# Schema.net
KiCad netlist of a schematic drawn in Altium Designer
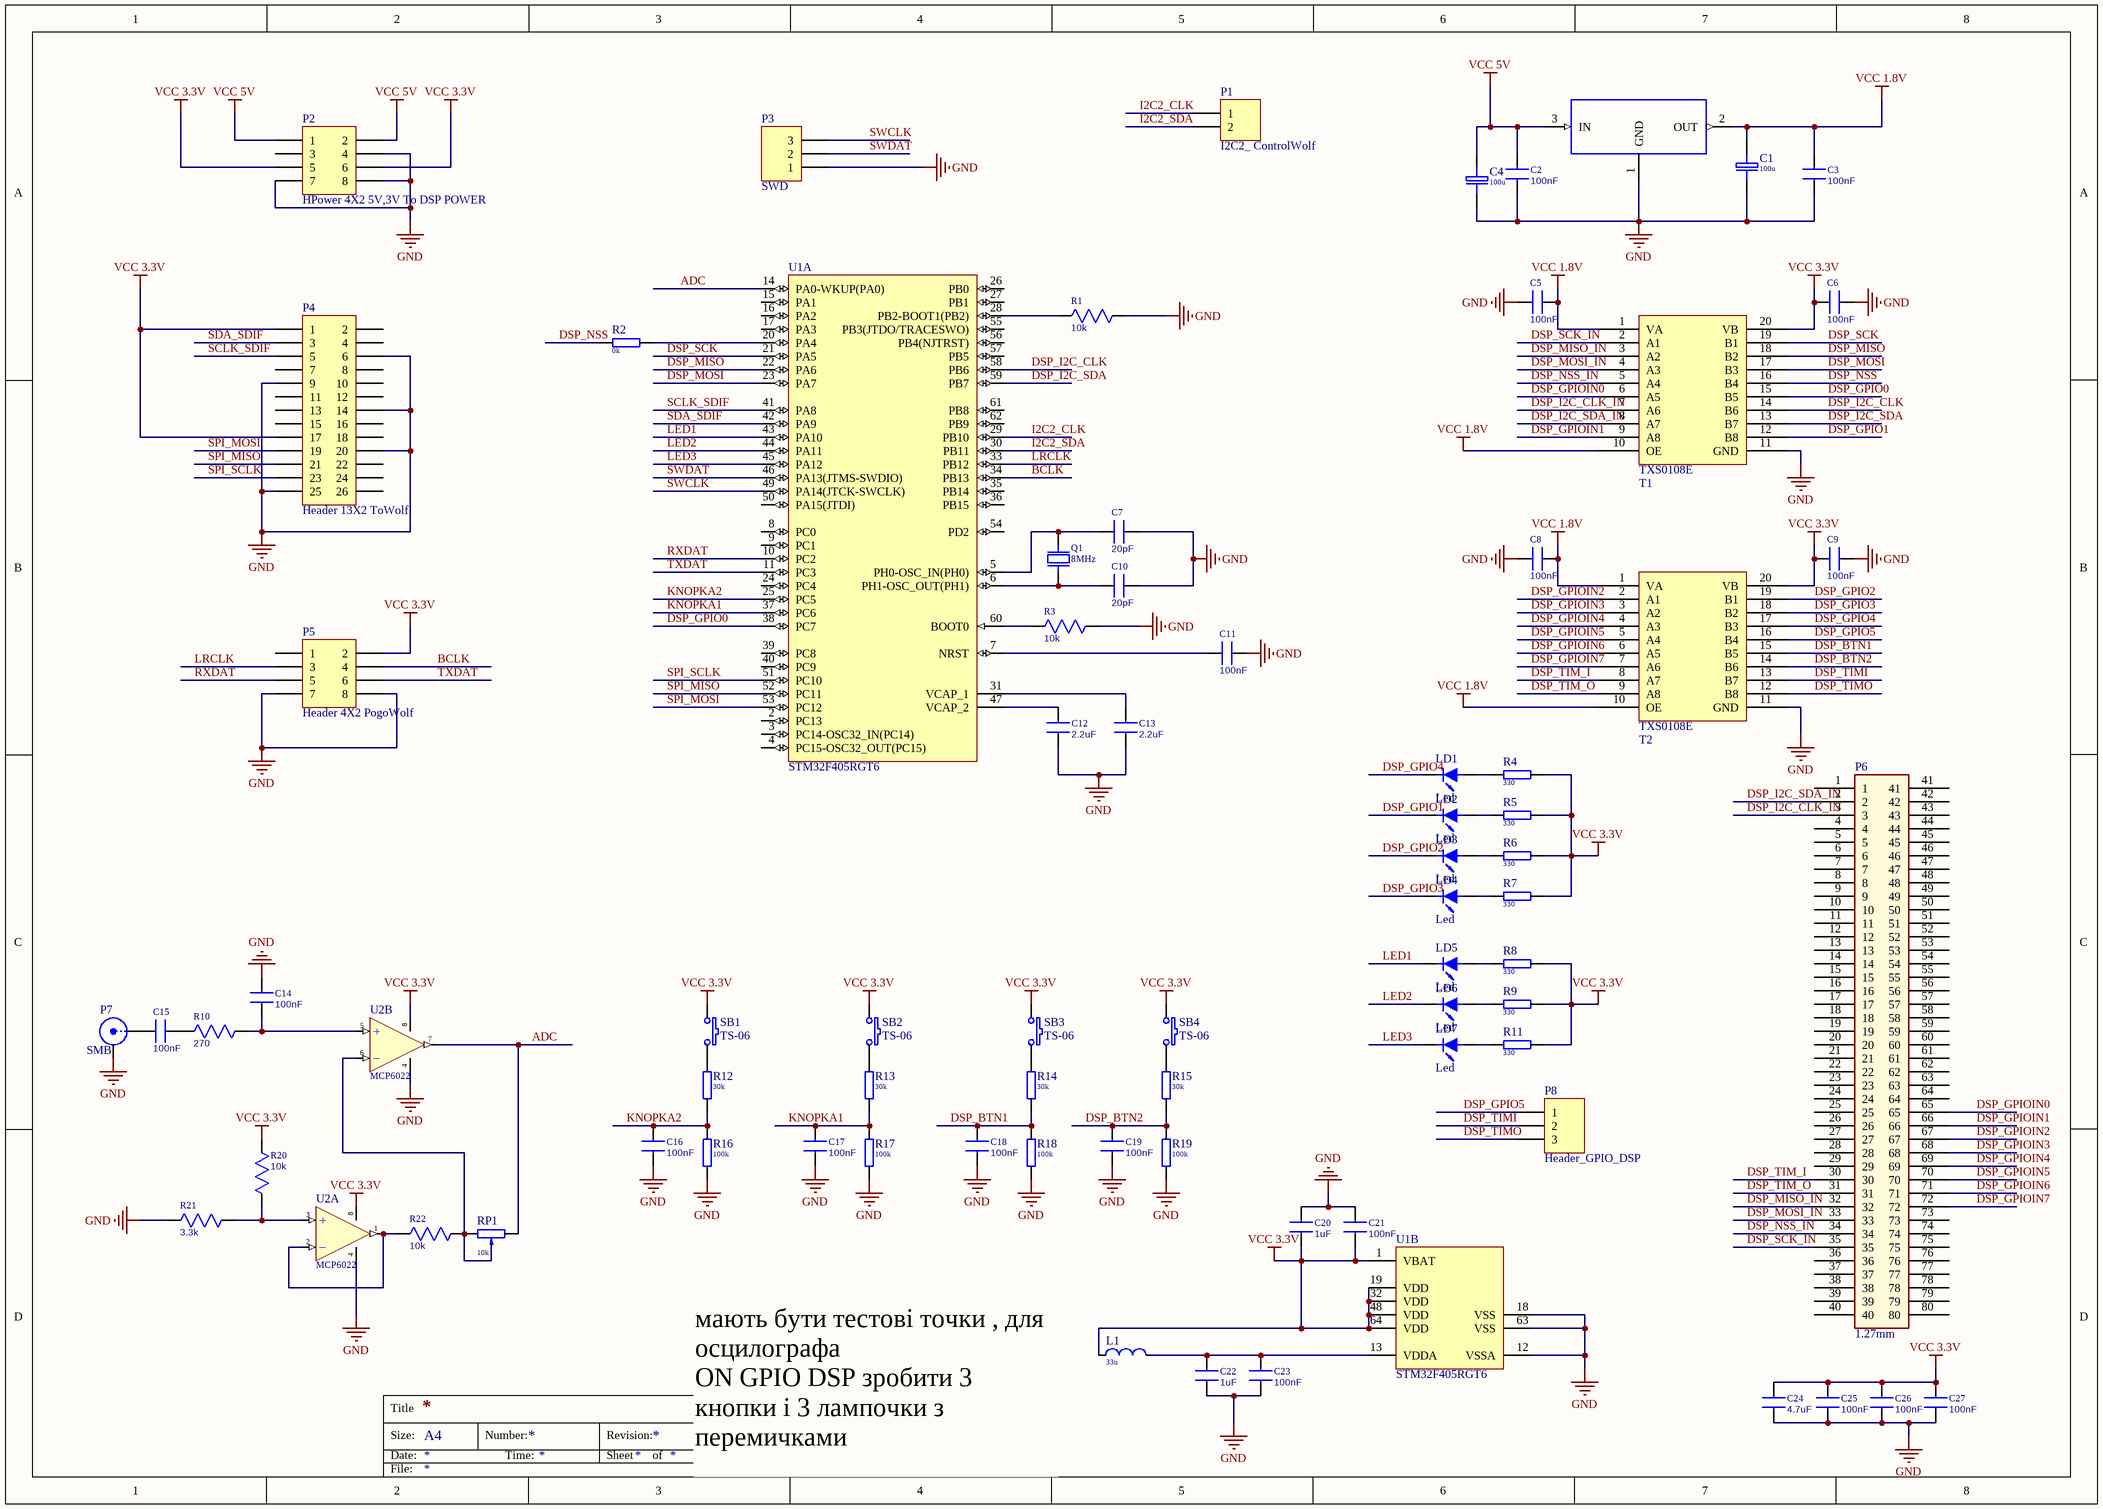
[diagram p0: Schema.SchDoc]

(export (version "E")
  (design (tool "Eeschema 10.0.6"))
  (components
    (comp (ref "1")
      (value "AMS1117-1.8")
      (footprint "SOT-223_AMS1117-3.3(Primary)")
      (libsource (lib "ams1117_33") (part "AMS1117-3.3"))
    )
    (comp (ref "C1")
      (value "100u")
      (footprint "El-d5-h11-F2.54")
      (description "35V")
      (libsource (lib "Cap-El") (part "10u-35V"))
    )
    (comp (ref "C2")
      (value "100nF")
      (footprint "C_0805")
      (description "Capacitor")
      (libsource (lib "AX_Altium_v2.3") (part "C0805"))
    )
    (comp (ref "C3")
      (value "100nF")
      (footprint "C_0805")
      (description "Capacitor")
      (libsource (lib "AX_Altium_v2.3") (part "C0805"))
    )
    (comp (ref "C4")
      (value "100u")
      (footprint "El-d5-h11-F2.54")
      (description "35V")
      (libsource (lib "Cap-El") (part "10u-35V"))
    )
    (comp (ref "C5")
      (value "100nF")
      (footprint "C_0805")
      (description "Capacitor")
      (libsource (lib "AX_Altium_v2.3") (part "C0805"))
    )
    (comp (ref "C6")
      (value "100nF")
      (footprint "C_0805")
      (description "Capacitor")
      (libsource (lib "AX_Altium_v2.3") (part "C0805"))
    )
    (comp (ref "C7")
      (value "20pF")
      (footprint "C_0805")
      (description "Capacitor")
      (libsource (lib "AX_Altium_v2.3") (part "C0805"))
    )
    (comp (ref "C8")
      (value "100nF")
      (footprint "C_0805")
      (description "Capacitor")
      (libsource (lib "AX_Altium_v2.3") (part "C0805"))
    )
    (comp (ref "C9")
      (value "100nF")
      (footprint "C_0805")
      (description "Capacitor")
      (libsource (lib "AX_Altium_v2.3") (part "C0805"))
    )
    (comp (ref "C10")
      (value "20pF")
      (footprint "C_0805")
      (description "Capacitor")
      (libsource (lib "AX_Altium_v2.3") (part "C0805"))
    )
    (comp (ref "C11")
      (value "100nF")
      (footprint "C_0805")
      (description "Capacitor")
      (libsource (lib "AX_Altium_v2.3") (part "C0805"))
    )
    (comp (ref "C12")
      (value "2.2uF")
      (footprint "C_0805")
      (description "Capacitor")
      (libsource (lib "AX_Altium_v2.3") (part "C0805"))
    )
    (comp (ref "C13")
      (value "2.2uF")
      (footprint "C_0805")
      (description "Capacitor")
      (libsource (lib "AX_Altium_v2.3") (part "C0805"))
    )
    (comp (ref "C14")
      (value "100nF")
      (footprint "C_0805")
      (description "Capacitor")
      (libsource (lib "AX_Altium_v2.3") (part "C0805"))
    )
    (comp (ref "C15")
      (value "100nF")
      (footprint "C_0805")
      (description "Capacitor")
      (libsource (lib "AX_Altium_v2.3") (part "C0805"))
    )
    (comp (ref "C16")
      (value "100nF")
      (footprint "C_0805")
      (description "Capacitor")
      (libsource (lib "AX_Altium_v2.3") (part "C0805"))
    )
    (comp (ref "C17")
      (value "100nF")
      (footprint "C_0805")
      (description "Capacitor")
      (libsource (lib "AX_Altium_v2.3") (part "C0805"))
    )
    (comp (ref "C18")
      (value "100nF")
      (footprint "C_0805")
      (description "Capacitor")
      (libsource (lib "AX_Altium_v2.3") (part "C0805"))
    )
    (comp (ref "C19")
      (value "100nF")
      (footprint "C_0805")
      (description "Capacitor")
      (libsource (lib "AX_Altium_v2.3") (part "C0805"))
    )
    (comp (ref "C20")
      (value "1uF")
      (footprint "C_0805")
      (description "Capacitor")
      (libsource (lib "AX_Altium_v2.3") (part "C0805"))
    )
    (comp (ref "C21")
      (value "100nF")
      (footprint "C_0805")
      (description "Capacitor")
      (libsource (lib "AX_Altium_v2.3") (part "C0805"))
    )
    (comp (ref "C22")
      (value "1uF")
      (footprint "C_0805")
      (description "Capacitor")
      (libsource (lib "AX_Altium_v2.3") (part "C0805"))
    )
    (comp (ref "C23")
      (value "100nF")
      (footprint "C_0805")
      (description "Capacitor")
      (libsource (lib "AX_Altium_v2.3") (part "C0805"))
    )
    (comp (ref "C24")
      (value "4.7uF")
      (footprint "C_0805")
      (description "Capacitor")
      (libsource (lib "AX_Altium_v2.3") (part "C0805"))
    )
    (comp (ref "C25")
      (value "100nF")
      (footprint "C_0805")
      (description "Capacitor")
      (libsource (lib "AX_Altium_v2.3") (part "C0805"))
    )
    (comp (ref "C26")
      (value "100nF")
      (footprint "C_0805")
      (description "Capacitor")
      (libsource (lib "AX_Altium_v2.3") (part "C0805"))
    )
    (comp (ref "C27")
      (value "100nF")
      (footprint "C_0805")
      (description "Capacitor")
      (libsource (lib "AX_Altium_v2.3") (part "C0805"))
    )
    (comp (ref "L1")
      (value "33u")
      (footprint "Dr-SD-75")
      (description "1.2A 0.15om 7.3x7.3x5mm")
      (libsource (lib "SMD-RCL") (part "L-SD-75 33uH"))
    )
    (comp (ref "LD1")
      (value "Led")
      (footprint "Led d3mm Blue")
      (description "3mm")
      (libsource (lib "Ind LED-LCD") (part "Led 3mm Blue"))
    )
    (comp (ref "LD2")
      (value "Led")
      (footprint "Led d3mm Blue")
      (description "3mm")
      (libsource (lib "Ind LED-LCD") (part "Led 3mm Blue"))
    )
    (comp (ref "LD3")
      (value "Led")
      (footprint "Led d3mm Blue")
      (description "3mm")
      (libsource (lib "Ind LED-LCD") (part "Led 3mm Blue"))
    )
    (comp (ref "LD4")
      (value "Led")
      (footprint "Led d3mm Blue")
      (description "3mm")
      (libsource (lib "Ind LED-LCD") (part "Led 3mm Blue"))
    )
    (comp (ref "LD5")
      (value "Led")
      (footprint "Led d3mm Blue")
      (description "3mm")
      (libsource (lib "Ind LED-LCD") (part "Led 3mm Blue"))
    )
    (comp (ref "LD6")
      (value "Led")
      (footprint "Led d3mm Blue")
      (description "3mm")
      (libsource (lib "Ind LED-LCD") (part "Led 3mm Blue"))
    )
    (comp (ref "LD7")
      (value "Led")
      (footprint "Led d3mm Blue")
      (description "3mm")
      (libsource (lib "Ind LED-LCD") (part "Led 3mm Blue"))
    )
    (comp (ref "P1")
      (value "I2C2_ ControlWolf")
      (footprint "HDR1X2")
      (description "Header, 2-Pin")
      (fields (field (name "PUBLISHER") "Altium Limited"))
      (libsource (lib "Miscellaneous Connectors") (part "Header 2"))
    )
    (comp (ref "P2")
      (value "HPower 4X2 5V,3V To DSP POWER")
      (footprint "HDR2X4")
      (description "Header, 4-Pin, Dual row")
      (fields (field (name "PUBLISHER") "Altium Limited"))
      (libsource (lib "Miscellaneous Connectors") (part "Header 4X2"))
    )
    (comp (ref "P3")
      (value "SWD")
      (footprint "HDR1X3")
      (description "Header, 3-Pin")
      (fields (field (name "PUBLISHER") "Altium Limited"))
      (libsource (lib "") (part "Header 3_1"))
    )
    (comp (ref "P4")
      (value "Header 13X2 ToWolf")
      (footprint "HDR2X13")
      (description "Header, 13-Pin, Dual row")
      (fields (field (name "PUBLISHER") "Altium Limited"))
      (libsource (lib "Miscellaneous Connectors") (part "Header 13X2"))
    )
    (comp (ref "P5")
      (value "Header 4X2 PogoWolf")
      (footprint "HDR2X4")
      (description "Header, 4-Pin, Dual row")
      (fields (field (name "PUBLISHER") "Altium Limited"))
      (libsource (lib "Miscellaneous Connectors") (part "Header 4X2"))
    )
    (comp (ref "P6")
      (value "1.27mm")
      (footprint "1.27mm-80pins-1:1.27mm-80p")
      (libsource (lib "1.27mm-80pins_1") (part "1.27mm Header"))
    )
    (comp (ref "P7")
      (value "SMB")
      (footprint "SMB_V-RJ45")
      (description "SMB Straight Connector")
      (fields (field (name "PUBLISHER") "Altium Limited"))
      (libsource (lib "Miscellaneous Connectors") (part "SMB"))
    )
    (comp (ref "P8")
      (value "Header_GPIO_DSP")
      (footprint "HDR1X3")
      (description "Header, 3-Pin")
      (fields (field (name "PUBLISHER") "Altium Limited"))
      (libsource (lib "Miscellaneous Connectors") (part "Header 3"))
    )
    (comp (ref "Q1") (value "8MHz") (footprint "HC49S") (libsource (lib "Devise") (part "Q")))
    (comp (ref "R1")
      (value "10k")
      (footprint "R_0805")
      (description "Resistor")
      (fields (field (name "Comment") "0"))
      (libsource (lib "AX_Altium_v2.3") (part "R0805"))
    )
    (comp (ref "R2")
      (value "0k")
      (footprint "R0805")
      (description "SMD 0805 0.1W 5% 150V")
      (libsource (lib "SMD-RCL") (part "R-0805"))
    )
    (comp (ref "R3")
      (value "10k")
      (footprint "R_0805")
      (description "Resistor")
      (fields (field (name "Comment") "0"))
      (libsource (lib "AX_Altium_v2.3") (part "R0805"))
    )
    (comp (ref "R4")
      (value "330")
      (footprint "R0805")
      (description "SMD 0805 0.1W 5% 150V")
      (libsource (lib "SMD-RCL") (part "R-0805"))
    )
    (comp (ref "R5")
      (value "330")
      (footprint "R0805")
      (description "SMD 0805 0.1W 5% 150V")
      (libsource (lib "SMD-RCL") (part "R-0805"))
    )
    (comp (ref "R6")
      (value "330")
      (footprint "R0805")
      (description "SMD 0805 0.1W 5% 150V")
      (libsource (lib "SMD-RCL") (part "R-0805"))
    )
    (comp (ref "R7")
      (value "330")
      (footprint "R0805")
      (description "SMD 0805 0.1W 5% 150V")
      (libsource (lib "SMD-RCL") (part "R-0805"))
    )
    (comp (ref "R8")
      (value "330")
      (footprint "R0805")
      (description "SMD 0805 0.1W 5% 150V")
      (libsource (lib "SMD-RCL") (part "R-0805"))
    )
    (comp (ref "R9")
      (value "330")
      (footprint "R0805")
      (description "SMD 0805 0.1W 5% 150V")
      (libsource (lib "SMD-RCL") (part "R-0805"))
    )
    (comp (ref "R10")
      (value "270")
      (footprint "R_0805")
      (description "Resistor")
      (fields (field (name "Comment") "0"))
      (libsource (lib "AX_Altium_v2.3") (part "R0805"))
    )
    (comp (ref "R11")
      (value "330")
      (footprint "R0805")
      (description "SMD 0805 0.1W 5% 150V")
      (libsource (lib "SMD-RCL") (part "R-0805"))
    )
    (comp (ref "R12")
      (value "30k")
      (footprint "R0805")
      (description "SMD 0805 0.1W 5% 150V")
      (libsource (lib "SMD-RCL") (part "R-0805"))
    )
    (comp (ref "R13")
      (value "30k")
      (footprint "R0805")
      (description "SMD 0805 0.1W 5% 150V")
      (libsource (lib "SMD-RCL") (part "R-0805"))
    )
    (comp (ref "R14")
      (value "30k")
      (footprint "R0805")
      (description "SMD 0805 0.1W 5% 150V")
      (libsource (lib "SMD-RCL") (part "R-0805"))
    )
    (comp (ref "R15")
      (value "30k")
      (footprint "R0805")
      (description "SMD 0805 0.1W 5% 150V")
      (libsource (lib "SMD-RCL") (part "R-0805"))
    )
    (comp (ref "R16")
      (value "100k")
      (footprint "R0805")
      (description "SMD 0805 0.1W 5% 150V")
      (libsource (lib "SMD-RCL") (part "R-0805"))
    )
    (comp (ref "R17")
      (value "100k")
      (footprint "R0805")
      (description "SMD 0805 0.1W 5% 150V")
      (libsource (lib "SMD-RCL") (part "R-0805"))
    )
    (comp (ref "R18")
      (value "100k")
      (footprint "R0805")
      (description "SMD 0805 0.1W 5% 150V")
      (libsource (lib "SMD-RCL") (part "R-0805"))
    )
    (comp (ref "R19")
      (value "100k")
      (footprint "R0805")
      (description "SMD 0805 0.1W 5% 150V")
      (libsource (lib "SMD-RCL") (part "R-0805"))
    )
    (comp (ref "R20")
      (value "10k")
      (footprint "R_0805")
      (description "Resistor")
      (fields (field (name "Comment") "0"))
      (libsource (lib "AX_Altium_v2.3") (part "R0805"))
    )
    (comp (ref "R21")
      (value "3.3k")
      (footprint "R_0805")
      (description "Resistor")
      (fields (field (name "Comment") "0"))
      (libsource (lib "AX_Altium_v2.3") (part "R0805"))
    )
    (comp (ref "R22")
      (value "10k")
      (footprint "R_0805")
      (description "Resistor")
      (fields (field (name "Comment") "0"))
      (libsource (lib "AX_Altium_v2.3") (part "R0805"))
    )
    (comp (ref "RP1")
      (value "10k")
      (footprint "R-Tr 6LV")
      (description "Тример 0,15W 6mm Вер. Piner")
      (libsource (lib "Rez-Axial Pot") (part "R-Tr 6LV"))
    )
    (comp (ref "SB1") (value "TS-06") (footprint "TS-06") (libsource (lib "Devise") (part "Buton TS-06")))
    (comp (ref "SB2") (value "TS-06") (footprint "TS-06") (libsource (lib "Devise") (part "Buton TS-06")))
    (comp (ref "SB3") (value "TS-06") (footprint "TS-06") (libsource (lib "Devise") (part "Buton TS-06")))
    (comp (ref "SB4") (value "TS-06") (footprint "TS-06") (libsource (lib "Devise") (part "Buton TS-06")))
    (comp (ref "T1")
      (value "Logic Level Converter")
      (footprint "TXS0108E")
      (libsource (lib "Library") (part "TXS0108E"))
    )
    (comp (ref "T2")
      (value "Logic Level Converter")
      (footprint "TXS0108E")
      (libsource (lib "Library") (part "TXS0108E"))
    )
    (comp (ref "U1")
      (value "STM32F405RGT6")
      (footprint "STM-LQFP64_N")
      (fields (field (name "MANUFACTURER") "STMicroelectronics"))
      (libsource (lib "STMicroelectronics STM32 F4") (part "STM32F405RGT6"))
    )
    (comp (ref "U2")
      (value "MCP6022")
      (footprint "SO8-150")
      (description "CMOS 0.15mV 1.2MHz R/R In/Out 110uA")
      (libsource (lib "Op Amp - Comp") (part "MCP6072"))
    )
  )
  (nets
    (net (code "1") (name "/ADC") (class "Default")
      (node (ref "RP1") (pin "3") (pinfunction "3_3") (pintype "passive"))
      (node (ref "U1") (pin "14") (pinfunction "PA0-WKUP(PA0)_14") (pintype "bidirectional"))
      (node (ref "U2") (pin "7") (pinfunction "OUT_7") (pintype "output"))
    )
    (net (code "2") (name "/BCLK") (class "Default")
      (node (ref "P5") (pin "4") (pinfunction "4_4") (pintype "passive"))
      (node (ref "U1") (pin "34") (pinfunction "PB13_34") (pintype "bidirectional"))
    )
    (net (code "3") (name "/DSP_BTN1") (class "Default")
      (node (ref "C18") (pin "2") (pintype "passive"))
      (node (ref "R14") (pin "2") (pinfunction "2_2") (pintype "passive"))
      (node (ref "R18") (pin "1") (pinfunction "1_1") (pintype "passive"))
      (node (ref "T2") (pin "15") (pinfunction "B5_15") (pintype "passive"))
    )
    (net (code "4") (name "/DSP_BTN2") (class "Default")
      (node (ref "C19") (pin "2") (pintype "passive"))
      (node (ref "R15") (pin "2") (pinfunction "2_2") (pintype "passive"))
      (node (ref "R19") (pin "1") (pinfunction "1_1") (pintype "passive"))
      (node (ref "T2") (pin "14") (pinfunction "B6_14") (pintype "passive"))
    )
    (net (code "5") (name "/DSP_GPIO0") (class "Default")
      (node (ref "T1") (pin "15") (pinfunction "B5_15") (pintype "passive"))
      (node (ref "U1") (pin "38") (pinfunction "PC7_38") (pintype "bidirectional"))
    )
    (net (code "6") (name "/DSP_GPIO1") (class "Default")
      (node (ref "LD2") (pin "2") (pinfunction "K_2") (pintype "passive"))
      (node (ref "T1") (pin "12") (pinfunction "B8_12") (pintype "passive"))
    )
    (net (code "7") (name "/DSP_GPIO2") (class "Default")
      (node (ref "LD3") (pin "2") (pinfunction "K_2") (pintype "passive"))
      (node (ref "T2") (pin "19") (pinfunction "B1_19") (pintype "passive"))
    )
    (net (code "8") (name "/DSP_GPIO3") (class "Default")
      (node (ref "LD4") (pin "2") (pinfunction "K_2") (pintype "passive"))
      (node (ref "T2") (pin "18") (pinfunction "B2_18") (pintype "passive"))
    )
    (net (code "9") (name "/DSP_GPIO4") (class "Default")
      (node (ref "LD1") (pin "2") (pinfunction "K_2") (pintype "passive"))
      (node (ref "T2") (pin "17") (pinfunction "B3_17") (pintype "passive"))
    )
    (net (code "10") (name "/DSP_GPIO5") (class "Default")
      (node (ref "P8") (pin "1") (pinfunction "1_1") (pintype "passive"))
      (node (ref "T2") (pin "16") (pinfunction "B4_16") (pintype "passive"))
    )
    (net (code "11") (name "/DSP_GPIOIN0") (class "Default")
      (node (ref "P6") (pin "65") (pinfunction "65_65") (pintype "passive"))
      (node (ref "T1") (pin "6") (pinfunction "A5_6") (pintype "passive"))
    )
    (net (code "12") (name "/DSP_GPIOIN1") (class "Default")
      (node (ref "P6") (pin "66") (pinfunction "66_66") (pintype "passive"))
      (node (ref "T1") (pin "9") (pinfunction "A8_9") (pintype "passive"))
    )
    (net (code "13") (name "/DSP_GPIOIN2") (class "Default")
      (node (ref "P6") (pin "67") (pinfunction "67_67") (pintype "passive"))
      (node (ref "T2") (pin "2") (pinfunction "A1_2") (pintype "passive"))
    )
    (net (code "14") (name "/DSP_GPIOIN3") (class "Default")
      (node (ref "P6") (pin "68") (pinfunction "68_68") (pintype "passive"))
      (node (ref "T2") (pin "3") (pinfunction "A2_3") (pintype "passive"))
    )
    (net (code "15") (name "/DSP_GPIOIN4") (class "Default")
      (node (ref "P6") (pin "69") (pinfunction "69_69") (pintype "passive"))
      (node (ref "T2") (pin "4") (pinfunction "A3_4") (pintype "passive"))
    )
    (net (code "16") (name "/DSP_GPIOIN5") (class "Default")
      (node (ref "P6") (pin "70") (pinfunction "70_70") (pintype "passive"))
      (node (ref "T2") (pin "5") (pinfunction "A4_5") (pintype "passive"))
    )
    (net (code "17") (name "/DSP_GPIOIN6") (class "Default")
      (node (ref "P6") (pin "71") (pinfunction "71_71") (pintype "passive"))
      (node (ref "T2") (pin "6") (pinfunction "A5_6") (pintype "passive"))
    )
    (net (code "18") (name "/DSP_GPIOIN7") (class "Default")
      (node (ref "P6") (pin "72") (pinfunction "72_72") (pintype "passive"))
      (node (ref "T2") (pin "7") (pinfunction "A6_7") (pintype "passive"))
    )
    (net (code "19") (name "/DSP_I2C_CLK") (class "Default")
      (node (ref "T1") (pin "14") (pinfunction "B6_14") (pintype "passive"))
      (node (ref "U1") (pin "58") (pinfunction "PB6_58") (pintype "bidirectional"))
    )
    (net (code "20") (name "/DSP_I2C_CLK_IN") (class "Default")
      (node (ref "P6") (pin "3") (pinfunction "3_3") (pintype "passive"))
      (node (ref "T1") (pin "7") (pinfunction "A6_7") (pintype "passive"))
    )
    (net (code "21") (name "/DSP_I2C_SDA") (class "Default")
      (node (ref "T1") (pin "13") (pinfunction "B7_13") (pintype "passive"))
      (node (ref "U1") (pin "59") (pinfunction "PB7_59") (pintype "bidirectional"))
    )
    (net (code "22") (name "/DSP_I2C_SDA_IN") (class "Default")
      (node (ref "P6") (pin "2") (pinfunction "2_2") (pintype "passive"))
      (node (ref "T1") (pin "8") (pinfunction "A7_8") (pintype "passive"))
    )
    (net (code "23") (name "/DSP_MISO") (class "Default")
      (node (ref "T1") (pin "18") (pinfunction "B2_18") (pintype "passive"))
      (node (ref "U1") (pin "22") (pinfunction "PA6_22") (pintype "bidirectional"))
    )
    (net (code "24") (name "/DSP_MISO_IN") (class "Default")
      (node (ref "P6") (pin "32") (pinfunction "32_32") (pintype "passive"))
      (node (ref "T1") (pin "3") (pinfunction "A2_3") (pintype "passive"))
    )
    (net (code "25") (name "/DSP_MOSI") (class "Default")
      (node (ref "T1") (pin "17") (pinfunction "B3_17") (pintype "passive"))
      (node (ref "U1") (pin "23") (pinfunction "PA7_23") (pintype "bidirectional"))
    )
    (net (code "26") (name "/DSP_MOSI_IN") (class "Default")
      (node (ref "P6") (pin "33") (pinfunction "33_33") (pintype "passive"))
      (node (ref "T1") (pin "4") (pinfunction "A3_4") (pintype "passive"))
    )
    (net (code "27") (name "/DSP_NSS") (class "Default")
      (node (ref "R2") (pin "1") (pinfunction "1_1") (pintype "passive"))
      (node (ref "T1") (pin "16") (pinfunction "B4_16") (pintype "passive"))
    )
    (net (code "28") (name "/DSP_NSS_IN") (class "Default")
      (node (ref "P6") (pin "34") (pinfunction "34_34") (pintype "passive"))
      (node (ref "T1") (pin "5") (pinfunction "A4_5") (pintype "passive"))
    )
    (net (code "29") (name "/DSP_SCK") (class "Default")
      (node (ref "T1") (pin "19") (pinfunction "B1_19") (pintype "passive"))
      (node (ref "U1") (pin "21") (pinfunction "PA5_21") (pintype "bidirectional"))
    )
    (net (code "30") (name "/DSP_SCK_IN") (class "Default")
      (node (ref "P6") (pin "35") (pinfunction "35_35") (pintype "passive"))
      (node (ref "T1") (pin "2") (pinfunction "A1_2") (pintype "passive"))
    )
    (net (code "31") (name "/DSP_TIMI") (class "Default")
      (node (ref "P8") (pin "2") (pinfunction "2_2") (pintype "passive"))
      (node (ref "T2") (pin "13") (pinfunction "B7_13") (pintype "passive"))
    )
    (net (code "32") (name "/DSP_TIMO") (class "Default")
      (node (ref "P8") (pin "3") (pinfunction "3_3") (pintype "passive"))
      (node (ref "T2") (pin "12") (pinfunction "B8_12") (pintype "passive"))
    )
    (net (code "33") (name "/DSP_TIM_I") (class "Default")
      (node (ref "P6") (pin "30") (pinfunction "30_30") (pintype "passive"))
      (node (ref "T2") (pin "8") (pinfunction "A7_8") (pintype "passive"))
    )
    (net (code "34") (name "/DSP_TIM_O") (class "Default")
      (node (ref "P6") (pin "31") (pinfunction "31_31") (pintype "passive"))
      (node (ref "T2") (pin "9") (pinfunction "A8_9") (pintype "passive"))
    )
    (net (code "35") (name "/I2C2_CLK") (class "Default")
      (node (ref "P1") (pin "1") (pinfunction "1_1") (pintype "passive"))
      (node (ref "U1") (pin "29") (pinfunction "PB10_29") (pintype "bidirectional"))
    )
    (net (code "36") (name "/I2C2_SDA") (class "Default")
      (node (ref "P1") (pin "2") (pinfunction "2_2") (pintype "passive"))
      (node (ref "U1") (pin "30") (pinfunction "PB11_30") (pintype "bidirectional"))
    )
    (net (code "37") (name "/KNOPKA1") (class "Default")
      (node (ref "C17") (pin "2") (pintype "passive"))
      (node (ref "R13") (pin "2") (pinfunction "2_2") (pintype "passive"))
      (node (ref "R17") (pin "1") (pinfunction "1_1") (pintype "passive"))
      (node (ref "U1") (pin "37") (pinfunction "PC6_37") (pintype "bidirectional"))
    )
    (net (code "38") (name "/KNOPKA2") (class "Default")
      (node (ref "C16") (pin "2") (pintype "passive"))
      (node (ref "R12") (pin "2") (pinfunction "2_2") (pintype "passive"))
      (node (ref "R16") (pin "1") (pinfunction "1_1") (pintype "passive"))
      (node (ref "U1") (pin "25") (pinfunction "PC5_25") (pintype "bidirectional"))
    )
    (net (code "39") (name "/LED1") (class "Default")
      (node (ref "LD5") (pin "2") (pinfunction "K_2") (pintype "passive"))
      (node (ref "U1") (pin "43") (pinfunction "PA10_43") (pintype "bidirectional"))
    )
    (net (code "40") (name "/LED2") (class "Default")
      (node (ref "LD6") (pin "2") (pinfunction "K_2") (pintype "passive"))
      (node (ref "U1") (pin "44") (pinfunction "PA11_44") (pintype "bidirectional"))
    )
    (net (code "41") (name "/LED3") (class "Default")
      (node (ref "LD7") (pin "2") (pinfunction "K_2") (pintype "passive"))
      (node (ref "U1") (pin "45") (pinfunction "PA12_45") (pintype "bidirectional"))
    )
    (net (code "42") (name "/LRCLK") (class "Default")
      (node (ref "P5") (pin "3") (pinfunction "3_3") (pintype "passive"))
      (node (ref "U1") (pin "33") (pinfunction "PB12_33") (pintype "bidirectional"))
    )
    (net (code "43") (name "/RXDAT") (class "Default")
      (node (ref "P5") (pin "5") (pinfunction "5_5") (pintype "passive"))
      (node (ref "U1") (pin "10") (pinfunction "PC2_10") (pintype "bidirectional"))
    )
    (net (code "44") (name "/SCLK_SDIF") (class "Default")
      (node (ref "P4") (pin "5") (pinfunction "5_5") (pintype "passive"))
      (node (ref "U1") (pin "41") (pinfunction "PA8_41") (pintype "bidirectional"))
    )
    (net (code "45") (name "/SDA_SDIF") (class "Default")
      (node (ref "P4") (pin "3") (pinfunction "3_3") (pintype "passive"))
      (node (ref "U1") (pin "42") (pinfunction "PA9_42") (pintype "bidirectional"))
    )
    (net (code "46") (name "/SPI_MISO") (class "Default")
      (node (ref "P4") (pin "21") (pinfunction "21_21") (pintype "passive"))
      (node (ref "U1") (pin "52") (pinfunction "PC11_52") (pintype "bidirectional"))
    )
    (net (code "47") (name "/SPI_MOSI") (class "Default")
      (node (ref "P4") (pin "19") (pinfunction "19_19") (pintype "passive"))
      (node (ref "U1") (pin "53") (pinfunction "PC12_53") (pintype "bidirectional"))
    )
    (net (code "48") (name "/SPI_SCLK") (class "Default")
      (node (ref "P4") (pin "23") (pinfunction "23_23") (pintype "passive"))
      (node (ref "U1") (pin "51") (pinfunction "PC10_51") (pintype "bidirectional"))
    )
    (net (code "49") (name "/SWCLK") (class "Default")
      (node (ref "P3") (pin "3") (pinfunction "3_3") (pintype "passive"))
      (node (ref "U1") (pin "49") (pinfunction "PA14(JTCK-SWCLK)_49") (pintype "bidirectional"))
    )
    (net (code "50") (name "/SWDAT") (class "Default")
      (node (ref "P3") (pin "2") (pinfunction "2_2") (pintype "passive"))
      (node (ref "U1") (pin "46") (pinfunction "PA13(JTMS-SWDIO)_46") (pintype "bidirectional"))
    )
    (net (code "51") (name "/TXDAT") (class "Default")
      (node (ref "P5") (pin "6") (pinfunction "6_6") (pintype "passive"))
      (node (ref "U1") (pin "11") (pinfunction "PC3_11") (pintype "bidirectional"))
    )
    (net (code "52") (name "GND") (class "Default")
      (node (ref "1") (pin "1") (pinfunction "GND_1") (pintype "passive"))
      (node (ref "C1") (pin "2") (pinfunction "2_2") (pintype "passive"))
      (node (ref "C10") (pin "1") (pintype "passive"))
      (node (ref "C11") (pin "1") (pintype "passive"))
      (node (ref "C12") (pin "1") (pintype "passive"))
      (node (ref "C13") (pin "1") (pintype "passive"))
      (node (ref "C14") (pin "1") (pintype "passive"))
      (node (ref "C16") (pin "1") (pintype "passive"))
      (node (ref "C17") (pin "1") (pintype "passive"))
      (node (ref "C18") (pin "1") (pintype "passive"))
      (node (ref "C19") (pin "1") (pintype "passive"))
      (node (ref "C2") (pin "1") (pintype "passive"))
      (node (ref "C20") (pin "2") (pintype "passive"))
      (node (ref "C21") (pin "2") (pintype "passive"))
      (node (ref "C22") (pin "1") (pintype "passive"))
      (node (ref "C23") (pin "1") (pintype "passive"))
      (node (ref "C24") (pin "1") (pintype "passive"))
      (node (ref "C25") (pin "1") (pintype "passive"))
      (node (ref "C26") (pin "1") (pintype "passive"))
      (node (ref "C27") (pin "1") (pintype "passive"))
      (node (ref "C3") (pin "1") (pintype "passive"))
      (node (ref "C4") (pin "2") (pinfunction "2_2") (pintype "passive"))
      (node (ref "C5") (pin "1") (pintype "passive"))
      (node (ref "C6") (pin "2") (pintype "passive"))
      (node (ref "C7") (pin "1") (pintype "passive"))
      (node (ref "C8") (pin "1") (pintype "passive"))
      (node (ref "C9") (pin "2") (pintype "passive"))
      (node (ref "P2") (pin "4") (pinfunction "4_4") (pintype "passive"))
      (node (ref "P2") (pin "7") (pinfunction "7_7") (pintype "passive"))
      (node (ref "P2") (pin "8") (pinfunction "8_8") (pintype "passive"))
      (node (ref "P3") (pin "1") (pinfunction "1_1") (pintype "passive"))
      (node (ref "P4") (pin "14") (pinfunction "14_14") (pintype "passive"))
      (node (ref "P4") (pin "20") (pinfunction "20_20") (pintype "passive"))
      (node (ref "P4") (pin "25") (pinfunction "25_25") (pintype "passive"))
      (node (ref "P4") (pin "6") (pinfunction "6_6") (pintype "passive"))
      (node (ref "P4") (pin "9") (pinfunction "9_9") (pintype "passive"))
      (node (ref "P5") (pin "7") (pinfunction "7_7") (pintype "passive"))
      (node (ref "P5") (pin "8") (pinfunction "8_8") (pintype "passive"))
      (node (ref "P7") (pin "2") (pinfunction "Y_2") (pintype "passive"))
      (node (ref "R1") (pin "1") (pintype "passive"))
      (node (ref "R16") (pin "2") (pinfunction "2_2") (pintype "passive"))
      (node (ref "R17") (pin "2") (pinfunction "2_2") (pintype "passive"))
      (node (ref "R18") (pin "2") (pinfunction "2_2") (pintype "passive"))
      (node (ref "R19") (pin "2") (pinfunction "2_2") (pintype "passive"))
      (node (ref "R21") (pin "1") (pintype "passive"))
      (node (ref "R3") (pin "1") (pintype "passive"))
      (node (ref "T1") (pin "11") (pinfunction "GND_11") (pintype "passive"))
      (node (ref "T2") (pin "11") (pinfunction "GND_11") (pintype "passive"))
      (node (ref "U1") (pin "12") (pinfunction "VSSA_12") (pintype "power_in"))
      (node (ref "U1") (pin "18") (pinfunction "VSS_18") (pintype "power_in"))
      (node (ref "U1") (pin "63") (pinfunction "VSS_63") (pintype "power_in"))
      (node (ref "U2") (pin "4") (pinfunction "V-_4") (pintype "power_in"))
    )
    (net (code "53") (name "Net-(C15-Pad2)") (class "Default")
      (node (ref "C15") (pin "2") (pintype "passive"))
      (node (ref "R10") (pin "1") (pintype "passive"))
    )
    (net (code "54") (name "Net-(LD1-A)") (class "Default")
      (node (ref "LD1") (pin "1") (pinfunction "A_1") (pintype "passive"))
      (node (ref "R4") (pin "2") (pinfunction "2_2") (pintype "passive"))
    )
    (net (code "55") (name "Net-(LD2-A)") (class "Default")
      (node (ref "LD2") (pin "1") (pinfunction "A_1") (pintype "passive"))
      (node (ref "R5") (pin "2") (pinfunction "2_2") (pintype "passive"))
    )
    (net (code "56") (name "Net-(LD3-A)") (class "Default")
      (node (ref "LD3") (pin "1") (pinfunction "A_1") (pintype "passive"))
      (node (ref "R6") (pin "2") (pinfunction "2_2") (pintype "passive"))
    )
    (net (code "57") (name "Net-(LD4-A)") (class "Default")
      (node (ref "LD4") (pin "1") (pinfunction "A_1") (pintype "passive"))
      (node (ref "R7") (pin "2") (pinfunction "2_2") (pintype "passive"))
    )
    (net (code "58") (name "Net-(LD5-A)") (class "Default")
      (node (ref "LD5") (pin "1") (pinfunction "A_1") (pintype "passive"))
      (node (ref "R8") (pin "2") (pinfunction "2_2") (pintype "passive"))
    )
    (net (code "59") (name "Net-(LD6-A)") (class "Default")
      (node (ref "LD6") (pin "1") (pinfunction "A_1") (pintype "passive"))
      (node (ref "R9") (pin "2") (pinfunction "2_2") (pintype "passive"))
    )
    (net (code "60") (name "Net-(LD7-A)") (class "Default")
      (node (ref "LD7") (pin "1") (pinfunction "A_1") (pintype "passive"))
      (node (ref "R11") (pin "2") (pinfunction "2_2") (pintype "passive"))
    )
    (net (code "61") (name "Net-(P7-X)") (class "Default")
      (node (ref "C15") (pin "1") (pintype "passive"))
      (node (ref "P7") (pin "1") (pinfunction "X_1") (pintype "passive"))
    )
    (net (code "62") (name "Net-(R12-Pad1)") (class "Default")
      (node (ref "R12") (pin "1") (pinfunction "1_1") (pintype "passive"))
      (node (ref "SB1") (pin "2") (pinfunction "2_2") (pintype "passive"))
    )
    (net (code "63") (name "Net-(R13-Pad1)") (class "Default")
      (node (ref "R13") (pin "1") (pinfunction "1_1") (pintype "passive"))
      (node (ref "SB2") (pin "2") (pinfunction "2_2") (pintype "passive"))
    )
    (net (code "64") (name "Net-(R14-Pad1)") (class "Default")
      (node (ref "R14") (pin "1") (pinfunction "1_1") (pintype "passive"))
      (node (ref "SB3") (pin "2") (pinfunction "2_2") (pintype "passive"))
    )
    (net (code "65") (name "Net-(R15-Pad1)") (class "Default")
      (node (ref "R15") (pin "1") (pinfunction "1_1") (pintype "passive"))
      (node (ref "SB4") (pin "2") (pinfunction "2_2") (pintype "passive"))
    )
    (net (code "66") (name "Net-(U1A-BOOT0)") (class "Default")
      (node (ref "R3") (pin "2") (pintype "passive"))
      (node (ref "U1") (pin "60") (pinfunction "BOOT0_60") (pintype "input"))
    )
    (net (code "67") (name "Net-(U1A-NRST)") (class "Default")
      (node (ref "C11") (pin "2") (pintype "passive"))
      (node (ref "U1") (pin "7") (pinfunction "NRST_7") (pintype "bidirectional"))
    )
    (net (code "68") (name "Net-(U1A-PA4)") (class "Default")
      (node (ref "R2") (pin "2") (pinfunction "2_2") (pintype "passive"))
      (node (ref "U1") (pin "20") (pinfunction "PA4_20") (pintype "bidirectional"))
    )
    (net (code "69") (name "Net-(U1A-PB2-BOOT1(PB2))") (class "Default")
      (node (ref "R1") (pin "2") (pintype "passive"))
      (node (ref "U1") (pin "28") (pinfunction "PB2-BOOT1(PB2)_28") (pintype "bidirectional"))
    )
    (net (code "70") (name "Net-(U1A-PH0-OSC_IN(PH0))") (class "Default")
      (node (ref "C7") (pin "2") (pintype "passive"))
      (node (ref "Q1") (pin "1") (pinfunction "1_1") (pintype "passive"))
      (node (ref "U1") (pin "5") (pinfunction "PH0-OSC_IN(PH0)_5") (pintype "bidirectional"))
    )
    (net (code "71") (name "Net-(U1A-PH1-OSC_OUT(PH1))") (class "Default")
      (node (ref "C10") (pin "2") (pintype "passive"))
      (node (ref "Q1") (pin "2") (pinfunction "2_2") (pintype "passive"))
      (node (ref "U1") (pin "6") (pinfunction "PH1-OSC_OUT(PH1)_6") (pintype "bidirectional"))
    )
    (net (code "72") (name "Net-(U1A-VCAP_1)") (class "Default")
      (node (ref "C13") (pin "2") (pintype "passive"))
      (node (ref "U1") (pin "31") (pinfunction "VCAP_1_31") (pintype "power_in"))
    )
    (net (code "73") (name "Net-(U1A-VCAP_2)") (class "Default")
      (node (ref "C12") (pin "2") (pintype "passive"))
      (node (ref "U1") (pin "47") (pinfunction "VCAP_2_47") (pintype "power_in"))
    )
    (net (code "74") (name "Net-(U1B-VDDA)") (class "Default")
      (node (ref "C22") (pin "2") (pintype "passive"))
      (node (ref "C23") (pin "2") (pintype "passive"))
      (node (ref "L1") (pin "2") (pinfunction "2_2") (pintype "passive"))
      (node (ref "U1") (pin "13") (pinfunction "VDDA_13") (pintype "power_in"))
    )
    (net (code "75") (name "Net-(U2A-+IN)") (class "Default")
      (node (ref "R20") (pin "2") (pintype "passive"))
      (node (ref "R21") (pin "2") (pintype "passive"))
      (node (ref "U2") (pin "3") (pinfunction "+IN_3") (pintype "input"))
    )
    (net (code "76") (name "Net-(U2A--IN)") (class "Default")
      (node (ref "R22") (pin "1") (pintype "passive"))
      (node (ref "U2") (pin "1") (pinfunction "OUT_1") (pintype "output"))
      (node (ref "U2") (pin "2") (pinfunction "-IN_2") (pintype "input"))
    )
    (net (code "77") (name "Net-(U2B-+IN)") (class "Default")
      (node (ref "C14") (pin "2") (pintype "passive"))
      (node (ref "R10") (pin "2") (pintype "passive"))
      (node (ref "U2") (pin "5") (pinfunction "+IN_5") (pintype "input"))
    )
    (net (code "78") (name "Net-(U2B--IN)") (class "Default")
      (node (ref "R22") (pin "2") (pintype "passive"))
      (node (ref "RP1") (pin "1") (pinfunction "1_1") (pintype "passive"))
      (node (ref "RP1") (pin "2") (pinfunction "2_2") (pintype "passive"))
      (node (ref "U2") (pin "6") (pinfunction "-IN_6") (pintype "input"))
    )
    (net (code "79") (name "VCC 1.8V") (class "Default")
      (node (ref "1") (pin "2") (pinfunction "OUT_2") (pintype "output"))
      (node (ref "C1") (pin "1") (pinfunction "1_1") (pintype "passive"))
      (node (ref "C3") (pin "2") (pintype "passive"))
      (node (ref "C5") (pin "2") (pintype "passive"))
      (node (ref "C8") (pin "2") (pintype "passive"))
      (node (ref "T1") (pin "1") (pinfunction "VA_1") (pintype "passive"))
      (node (ref "T1") (pin "10") (pinfunction "OE_10") (pintype "passive"))
      (node (ref "T2") (pin "1") (pinfunction "VA_1") (pintype "passive"))
      (node (ref "T2") (pin "10") (pinfunction "OE_10") (pintype "passive"))
    )
    (net (code "80") (name "VCC 3.3V") (class "Default")
      (node (ref "C20") (pin "1") (pintype "passive"))
      (node (ref "C21") (pin "1") (pintype "passive"))
      (node (ref "C24") (pin "2") (pintype "passive"))
      (node (ref "C25") (pin "2") (pintype "passive"))
      (node (ref "C26") (pin "2") (pintype "passive"))
      (node (ref "C27") (pin "2") (pintype "passive"))
      (node (ref "C6") (pin "1") (pintype "passive"))
      (node (ref "C9") (pin "1") (pintype "passive"))
      (node (ref "L1") (pin "1") (pinfunction "1_1") (pintype "passive"))
      (node (ref "P2") (pin "5") (pinfunction "5_5") (pintype "passive"))
      (node (ref "P2") (pin "6") (pinfunction "6_6") (pintype "passive"))
      (node (ref "P4") (pin "1") (pinfunction "1_1") (pintype "passive"))
      (node (ref "P4") (pin "17") (pinfunction "17_17") (pintype "passive"))
      (node (ref "P5") (pin "2") (pinfunction "2_2") (pintype "passive"))
      (node (ref "R11") (pin "1") (pinfunction "1_1") (pintype "passive"))
      (node (ref "R20") (pin "1") (pintype "passive"))
      (node (ref "R4") (pin "1") (pinfunction "1_1") (pintype "passive"))
      (node (ref "R5") (pin "1") (pinfunction "1_1") (pintype "passive"))
      (node (ref "R6") (pin "1") (pinfunction "1_1") (pintype "passive"))
      (node (ref "R7") (pin "1") (pinfunction "1_1") (pintype "passive"))
      (node (ref "R8") (pin "1") (pinfunction "1_1") (pintype "passive"))
      (node (ref "R9") (pin "1") (pinfunction "1_1") (pintype "passive"))
      (node (ref "SB1") (pin "1") (pinfunction "1_1") (pintype "passive"))
      (node (ref "SB2") (pin "1") (pinfunction "1_1") (pintype "passive"))
      (node (ref "SB3") (pin "1") (pinfunction "1_1") (pintype "passive"))
      (node (ref "SB4") (pin "1") (pinfunction "1_1") (pintype "passive"))
      (node (ref "T1") (pin "20") (pinfunction "VB_20") (pintype "passive"))
      (node (ref "T2") (pin "20") (pinfunction "VB_20") (pintype "passive"))
      (node (ref "U1") (pin "1") (pinfunction "VBAT_1") (pintype "power_in"))
      (node (ref "U1") (pin "19") (pinfunction "VDD_19") (pintype "power_in"))
      (node (ref "U1") (pin "32") (pinfunction "VDD_32") (pintype "power_in"))
      (node (ref "U1") (pin "48") (pinfunction "VDD_48") (pintype "power_in"))
      (node (ref "U1") (pin "64") (pinfunction "VDD_64") (pintype "power_in"))
      (node (ref "U2") (pin "8") (pinfunction "V+_8") (pintype "power_in"))
    )
    (net (code "81") (name "VCC 5V") (class "Default")
      (node (ref "1") (pin "3") (pinfunction "IN_3") (pintype "input"))
      (node (ref "C2") (pin "2") (pintype "passive"))
      (node (ref "C4") (pin "1") (pinfunction "1_1") (pintype "passive"))
      (node (ref "P2") (pin "1") (pinfunction "1_1") (pintype "passive"))
      (node (ref "P2") (pin "2") (pinfunction "2_2") (pintype "passive"))
    )
    (net (code "82") (name "unconnected-(P2-Pad3)") (class "Default")
      (node (ref "P2") (pin "3") (pinfunction "3_3") (pintype "passive"))
    )
    (net (code "83") (name "unconnected-(P4-Pad2)") (class "Default")
      (node (ref "P4") (pin "2") (pinfunction "2_2") (pintype "passive"))
    )
    (net (code "84") (name "unconnected-(P4-Pad4)") (class "Default")
      (node (ref "P4") (pin "4") (pinfunction "4_4") (pintype "passive"))
    )
    (net (code "85") (name "unconnected-(P4-Pad7)") (class "Default")
      (node (ref "P4") (pin "7") (pinfunction "7_7") (pintype "passive"))
    )
    (net (code "86") (name "unconnected-(P4-Pad8)") (class "Default")
      (node (ref "P4") (pin "8") (pinfunction "8_8") (pintype "passive"))
    )
    (net (code "87") (name "unconnected-(P4-Pad10)") (class "Default")
      (node (ref "P4") (pin "10") (pinfunction "10_10") (pintype "passive"))
    )
    (net (code "88") (name "unconnected-(P4-Pad11)") (class "Default")
      (node (ref "P4") (pin "11") (pinfunction "11_11") (pintype "passive"))
    )
    (net (code "89") (name "unconnected-(P4-Pad12)") (class "Default")
      (node (ref "P4") (pin "12") (pinfunction "12_12") (pintype "passive"))
    )
    (net (code "90") (name "unconnected-(P4-Pad13)") (class "Default")
      (node (ref "P4") (pin "13") (pinfunction "13_13") (pintype "passive"))
    )
    (net (code "91") (name "unconnected-(P4-Pad15)") (class "Default")
      (node (ref "P4") (pin "15") (pinfunction "15_15") (pintype "passive"))
    )
    (net (code "92") (name "unconnected-(P4-Pad16)") (class "Default")
      (node (ref "P4") (pin "16") (pinfunction "16_16") (pintype "passive"))
    )
    (net (code "93") (name "unconnected-(P4-Pad18)") (class "Default")
      (node (ref "P4") (pin "18") (pinfunction "18_18") (pintype "passive"))
    )
    (net (code "94") (name "unconnected-(P4-Pad22)") (class "Default")
      (node (ref "P4") (pin "22") (pinfunction "22_22") (pintype "passive"))
    )
    (net (code "95") (name "unconnected-(P4-Pad24)") (class "Default")
      (node (ref "P4") (pin "24") (pinfunction "24_24") (pintype "passive"))
    )
    (net (code "96") (name "unconnected-(P4-Pad26)") (class "Default")
      (node (ref "P4") (pin "26") (pinfunction "26_26") (pintype "passive"))
    )
    (net (code "97") (name "unconnected-(P5-Pad1)") (class "Default")
      (node (ref "P5") (pin "1") (pinfunction "1_1") (pintype "passive"))
    )
    (net (code "98") (name "unconnected-(P6-Pad1)") (class "Default")
      (node (ref "P6") (pin "1") (pinfunction "1_1") (pintype "passive"))
    )
    (net (code "99") (name "unconnected-(P6-Pad4)") (class "Default")
      (node (ref "P6") (pin "4") (pinfunction "4_4") (pintype "passive"))
    )
    (net (code "100") (name "unconnected-(P6-Pad5)") (class "Default")
      (node (ref "P6") (pin "5") (pinfunction "5_5") (pintype "passive"))
    )
    (net (code "101") (name "unconnected-(P6-Pad6)") (class "Default")
      (node (ref "P6") (pin "6") (pinfunction "6_6") (pintype "passive"))
    )
    (net (code "102") (name "unconnected-(P6-Pad7)") (class "Default")
      (node (ref "P6") (pin "7") (pinfunction "7_7") (pintype "passive"))
    )
    (net (code "103") (name "unconnected-(P6-Pad8)") (class "Default")
      (node (ref "P6") (pin "8") (pinfunction "8_8") (pintype "passive"))
    )
    (net (code "104") (name "unconnected-(P6-Pad9)") (class "Default")
      (node (ref "P6") (pin "9") (pinfunction "9_9") (pintype "passive"))
    )
    (net (code "105") (name "unconnected-(P6-Pad10)") (class "Default")
      (node (ref "P6") (pin "10") (pinfunction "10_10") (pintype "passive"))
    )
    (net (code "106") (name "unconnected-(P6-Pad11)") (class "Default")
      (node (ref "P6") (pin "11") (pinfunction "11_11") (pintype "passive"))
    )
    (net (code "107") (name "unconnected-(P6-Pad12)") (class "Default")
      (node (ref "P6") (pin "12") (pinfunction "12_12") (pintype "passive"))
    )
    (net (code "108") (name "unconnected-(P6-Pad13)") (class "Default")
      (node (ref "P6") (pin "13") (pinfunction "13_13") (pintype "passive"))
    )
    (net (code "109") (name "unconnected-(P6-Pad14)") (class "Default")
      (node (ref "P6") (pin "14") (pinfunction "14_14") (pintype "passive"))
    )
    (net (code "110") (name "unconnected-(P6-Pad15)") (class "Default")
      (node (ref "P6") (pin "15") (pinfunction "15_15") (pintype "passive"))
    )
    (net (code "111") (name "unconnected-(P6-Pad16)") (class "Default")
      (node (ref "P6") (pin "16") (pinfunction "16_16") (pintype "passive"))
    )
    (net (code "112") (name "unconnected-(P6-Pad17)") (class "Default")
      (node (ref "P6") (pin "17") (pinfunction "17_17") (pintype "passive"))
    )
    (net (code "113") (name "unconnected-(P6-Pad18)") (class "Default")
      (node (ref "P6") (pin "18") (pinfunction "18_18") (pintype "passive"))
    )
    (net (code "114") (name "unconnected-(P6-Pad19)") (class "Default")
      (node (ref "P6") (pin "19") (pinfunction "19_19") (pintype "passive"))
    )
    (net (code "115") (name "unconnected-(P6-Pad20)") (class "Default")
      (node (ref "P6") (pin "20") (pinfunction "20_20") (pintype "passive"))
    )
    (net (code "116") (name "unconnected-(P6-Pad21)") (class "Default")
      (node (ref "P6") (pin "21") (pinfunction "21_21") (pintype "passive"))
    )
    (net (code "117") (name "unconnected-(P6-Pad22)") (class "Default")
      (node (ref "P6") (pin "22") (pinfunction "22_22") (pintype "passive"))
    )
    (net (code "118") (name "unconnected-(P6-Pad23)") (class "Default")
      (node (ref "P6") (pin "23") (pinfunction "23_23") (pintype "passive"))
    )
    (net (code "119") (name "unconnected-(P6-Pad24)") (class "Default")
      (node (ref "P6") (pin "24") (pinfunction "24_24") (pintype "passive"))
    )
    (net (code "120") (name "unconnected-(P6-Pad25)") (class "Default")
      (node (ref "P6") (pin "25") (pinfunction "25_25") (pintype "passive"))
    )
    (net (code "121") (name "unconnected-(P6-Pad26)") (class "Default")
      (node (ref "P6") (pin "26") (pinfunction "26_26") (pintype "passive"))
    )
    (net (code "122") (name "unconnected-(P6-Pad27)") (class "Default")
      (node (ref "P6") (pin "27") (pinfunction "27_27") (pintype "passive"))
    )
    (net (code "123") (name "unconnected-(P6-Pad28)") (class "Default")
      (node (ref "P6") (pin "28") (pinfunction "28_28") (pintype "passive"))
    )
    (net (code "124") (name "unconnected-(P6-Pad29)") (class "Default")
      (node (ref "P6") (pin "29") (pinfunction "29_29") (pintype "passive"))
    )
    (net (code "125") (name "unconnected-(P6-Pad36)") (class "Default")
      (node (ref "P6") (pin "36") (pinfunction "36_36") (pintype "passive"))
    )
    (net (code "126") (name "unconnected-(P6-Pad37)") (class "Default")
      (node (ref "P6") (pin "37") (pinfunction "37_37") (pintype "passive"))
    )
    (net (code "127") (name "unconnected-(P6-Pad38)") (class "Default")
      (node (ref "P6") (pin "38") (pinfunction "38_38") (pintype "passive"))
    )
    (net (code "128") (name "unconnected-(P6-Pad39)") (class "Default")
      (node (ref "P6") (pin "39") (pinfunction "39_39") (pintype "passive"))
    )
    (net (code "129") (name "unconnected-(P6-Pad40)") (class "Default")
      (node (ref "P6") (pin "40") (pinfunction "40_40") (pintype "passive"))
    )
    (net (code "130") (name "unconnected-(P6-Pad41)") (class "Default")
      (node (ref "P6") (pin "41") (pinfunction "41_41") (pintype "passive"))
    )
    (net (code "131") (name "unconnected-(P6-Pad42)") (class "Default")
      (node (ref "P6") (pin "42") (pinfunction "42_42") (pintype "passive"))
    )
    (net (code "132") (name "unconnected-(P6-Pad43)") (class "Default")
      (node (ref "P6") (pin "43") (pinfunction "43_43") (pintype "passive"))
    )
    (net (code "133") (name "unconnected-(P6-Pad44)") (class "Default")
      (node (ref "P6") (pin "44") (pinfunction "44_44") (pintype "passive"))
    )
    (net (code "134") (name "unconnected-(P6-Pad45)") (class "Default")
      (node (ref "P6") (pin "45") (pinfunction "45_45") (pintype "passive"))
    )
    (net (code "135") (name "unconnected-(P6-Pad46)") (class "Default")
      (node (ref "P6") (pin "46") (pinfunction "46_46") (pintype "passive"))
    )
    (net (code "136") (name "unconnected-(P6-Pad47)") (class "Default")
      (node (ref "P6") (pin "47") (pinfunction "47_47") (pintype "passive"))
    )
    (net (code "137") (name "unconnected-(P6-Pad48)") (class "Default")
      (node (ref "P6") (pin "48") (pinfunction "48_48") (pintype "passive"))
    )
    (net (code "138") (name "unconnected-(P6-Pad49)") (class "Default")
      (node (ref "P6") (pin "49") (pinfunction "49_49") (pintype "passive"))
    )
    (net (code "139") (name "unconnected-(P6-Pad50)") (class "Default")
      (node (ref "P6") (pin "50") (pinfunction "50_50") (pintype "passive"))
    )
    (net (code "140") (name "unconnected-(P6-Pad51)") (class "Default")
      (node (ref "P6") (pin "51") (pinfunction "51_51") (pintype "passive"))
    )
    (net (code "141") (name "unconnected-(P6-Pad52)") (class "Default")
      (node (ref "P6") (pin "52") (pinfunction "52_52") (pintype "passive"))
    )
    (net (code "142") (name "unconnected-(P6-Pad53)") (class "Default")
      (node (ref "P6") (pin "53") (pinfunction "53_53") (pintype "passive"))
    )
    (net (code "143") (name "unconnected-(P6-Pad54)") (class "Default")
      (node (ref "P6") (pin "54") (pinfunction "54_54") (pintype "passive"))
    )
    (net (code "144") (name "unconnected-(P6-Pad55)") (class "Default")
      (node (ref "P6") (pin "55") (pinfunction "55_55") (pintype "passive"))
    )
    (net (code "145") (name "unconnected-(P6-Pad56)") (class "Default")
      (node (ref "P6") (pin "56") (pinfunction "56_56") (pintype "passive"))
    )
    (net (code "146") (name "unconnected-(P6-Pad57)") (class "Default")
      (node (ref "P6") (pin "57") (pinfunction "57_57") (pintype "passive"))
    )
    (net (code "147") (name "unconnected-(P6-Pad58)") (class "Default")
      (node (ref "P6") (pin "58") (pinfunction "58_58") (pintype "passive"))
    )
    (net (code "148") (name "unconnected-(P6-Pad59)") (class "Default")
      (node (ref "P6") (pin "59") (pinfunction "59_59") (pintype "passive"))
    )
    (net (code "149") (name "unconnected-(P6-Pad60)") (class "Default")
      (node (ref "P6") (pin "60") (pinfunction "60_60") (pintype "passive"))
    )
    (net (code "150") (name "unconnected-(P6-Pad61)") (class "Default")
      (node (ref "P6") (pin "61") (pinfunction "61_61") (pintype "passive"))
    )
    (net (code "151") (name "unconnected-(P6-Pad62)") (class "Default")
      (node (ref "P6") (pin "62") (pinfunction "62_62") (pintype "passive"))
    )
    (net (code "152") (name "unconnected-(P6-Pad63)") (class "Default")
      (node (ref "P6") (pin "63") (pinfunction "63_63") (pintype "passive"))
    )
    (net (code "153") (name "unconnected-(P6-Pad64)") (class "Default")
      (node (ref "P6") (pin "64") (pinfunction "64_64") (pintype "passive"))
    )
    (net (code "154") (name "unconnected-(P6-Pad73)") (class "Default")
      (node (ref "P6") (pin "73") (pinfunction "73_73") (pintype "passive"))
    )
    (net (code "155") (name "unconnected-(P6-Pad74)") (class "Default")
      (node (ref "P6") (pin "74") (pinfunction "74_74") (pintype "passive"))
    )
    (net (code "156") (name "unconnected-(P6-Pad75)") (class "Default")
      (node (ref "P6") (pin "75") (pinfunction "75_75") (pintype "passive"))
    )
    (net (code "157") (name "unconnected-(P6-Pad76)") (class "Default")
      (node (ref "P6") (pin "76") (pinfunction "76_76") (pintype "passive"))
    )
    (net (code "158") (name "unconnected-(P6-Pad77)") (class "Default")
      (node (ref "P6") (pin "77") (pinfunction "77_77") (pintype "passive"))
    )
    (net (code "159") (name "unconnected-(P6-Pad78)") (class "Default")
      (node (ref "P6") (pin "78") (pinfunction "78_78") (pintype "passive"))
    )
    (net (code "160") (name "unconnected-(P6-Pad79)") (class "Default")
      (node (ref "P6") (pin "79") (pinfunction "79_79") (pintype "passive"))
    )
    (net (code "161") (name "unconnected-(P6-Pad80)") (class "Default")
      (node (ref "P6") (pin "80") (pinfunction "80_80") (pintype "passive"))
    )
    (net (code "162") (name "unconnected-(U1A-PA1-Pad15)") (class "Default")
      (node (ref "U1") (pin "15") (pinfunction "PA1_15") (pintype "bidirectional"))
    )
    (net (code "163") (name "unconnected-(U1A-PA2-Pad16)") (class "Default")
      (node (ref "U1") (pin "16") (pinfunction "PA2_16") (pintype "bidirectional"))
    )
    (net (code "164") (name "unconnected-(U1A-PA3-Pad17)") (class "Default")
      (node (ref "U1") (pin "17") (pinfunction "PA3_17") (pintype "bidirectional"))
    )
    (net (code "165") (name "unconnected-(U1A-PA15(JTDI)-Pad50)") (class "Default")
      (node (ref "U1") (pin "50") (pinfunction "PA15(JTDI)_50") (pintype "bidirectional"))
    )
    (net (code "166") (name "unconnected-(U1A-PB0-Pad26)") (class "Default")
      (node (ref "U1") (pin "26") (pinfunction "PB0_26") (pintype "bidirectional"))
    )
    (net (code "167") (name "unconnected-(U1A-PB1-Pad27)") (class "Default")
      (node (ref "U1") (pin "27") (pinfunction "PB1_27") (pintype "bidirectional"))
    )
    (net (code "168") (name "unconnected-(U1A-PB3(JTDO{slash}TRACESWO)-Pad55)") (class "Default")
      (node (ref "U1") (pin "55") (pinfunction "PB3(JTDO/TRACESWO)_55") (pintype "bidirectional"))
    )
    (net (code "169") (name "unconnected-(U1A-PB4(NJTRST)-Pad56)") (class "Default")
      (node (ref "U1") (pin "56") (pinfunction "PB4(NJTRST)_56") (pintype "bidirectional"))
    )
    (net (code "170") (name "unconnected-(U1A-PB5-Pad57)") (class "Default")
      (node (ref "U1") (pin "57") (pinfunction "PB5_57") (pintype "bidirectional"))
    )
    (net (code "171") (name "unconnected-(U1A-PB8-Pad61)") (class "Default")
      (node (ref "U1") (pin "61") (pinfunction "PB8_61") (pintype "bidirectional"))
    )
    (net (code "172") (name "unconnected-(U1A-PB9-Pad62)") (class "Default")
      (node (ref "U1") (pin "62") (pinfunction "PB9_62") (pintype "bidirectional"))
    )
    (net (code "173") (name "unconnected-(U1A-PB14-Pad35)") (class "Default")
      (node (ref "U1") (pin "35") (pinfunction "PB14_35") (pintype "bidirectional"))
    )
    (net (code "174") (name "unconnected-(U1A-PB15-Pad36)") (class "Default")
      (node (ref "U1") (pin "36") (pinfunction "PB15_36") (pintype "bidirectional"))
    )
    (net (code "175") (name "unconnected-(U1A-PC0-Pad8)") (class "Default")
      (node (ref "U1") (pin "8") (pinfunction "PC0_8") (pintype "bidirectional"))
    )
    (net (code "176") (name "unconnected-(U1A-PC1-Pad9)") (class "Default")
      (node (ref "U1") (pin "9") (pinfunction "PC1_9") (pintype "bidirectional"))
    )
    (net (code "177") (name "unconnected-(U1A-PC4-Pad24)") (class "Default")
      (node (ref "U1") (pin "24") (pinfunction "PC4_24") (pintype "bidirectional"))
    )
    (net (code "178") (name "unconnected-(U1A-PC8-Pad39)") (class "Default")
      (node (ref "U1") (pin "39") (pinfunction "PC8_39") (pintype "bidirectional"))
    )
    (net (code "179") (name "unconnected-(U1A-PC9-Pad40)") (class "Default")
      (node (ref "U1") (pin "40") (pinfunction "PC9_40") (pintype "bidirectional"))
    )
    (net (code "180") (name "unconnected-(U1A-PC13-Pad2)") (class "Default")
      (node (ref "U1") (pin "2") (pinfunction "PC13_2") (pintype "bidirectional"))
    )
    (net (code "181") (name "unconnected-(U1A-PC14-OSC32_IN(PC14)-Pad3)") (class "Default")
      (node (ref "U1") (pin "3") (pinfunction "PC14-OSC32_IN(PC14)_3") (pintype "bidirectional"))
    )
    (net (code "182") (name "unconnected-(U1A-PC15-OSC32_OUT(PC15)-Pad4)") (class "Default")
      (node (ref "U1") (pin "4") (pinfunction "PC15-OSC32_OUT(PC15)_4") (pintype "bidirectional"))
    )
    (net (code "183") (name "unconnected-(U1A-PD2-Pad54)") (class "Default")
      (node (ref "U1") (pin "54") (pinfunction "PD2_54") (pintype "bidirectional"))
    )
  )
)
